# 02_MISC.net
KiCad netlist of a schematic drawn in Altium Designer
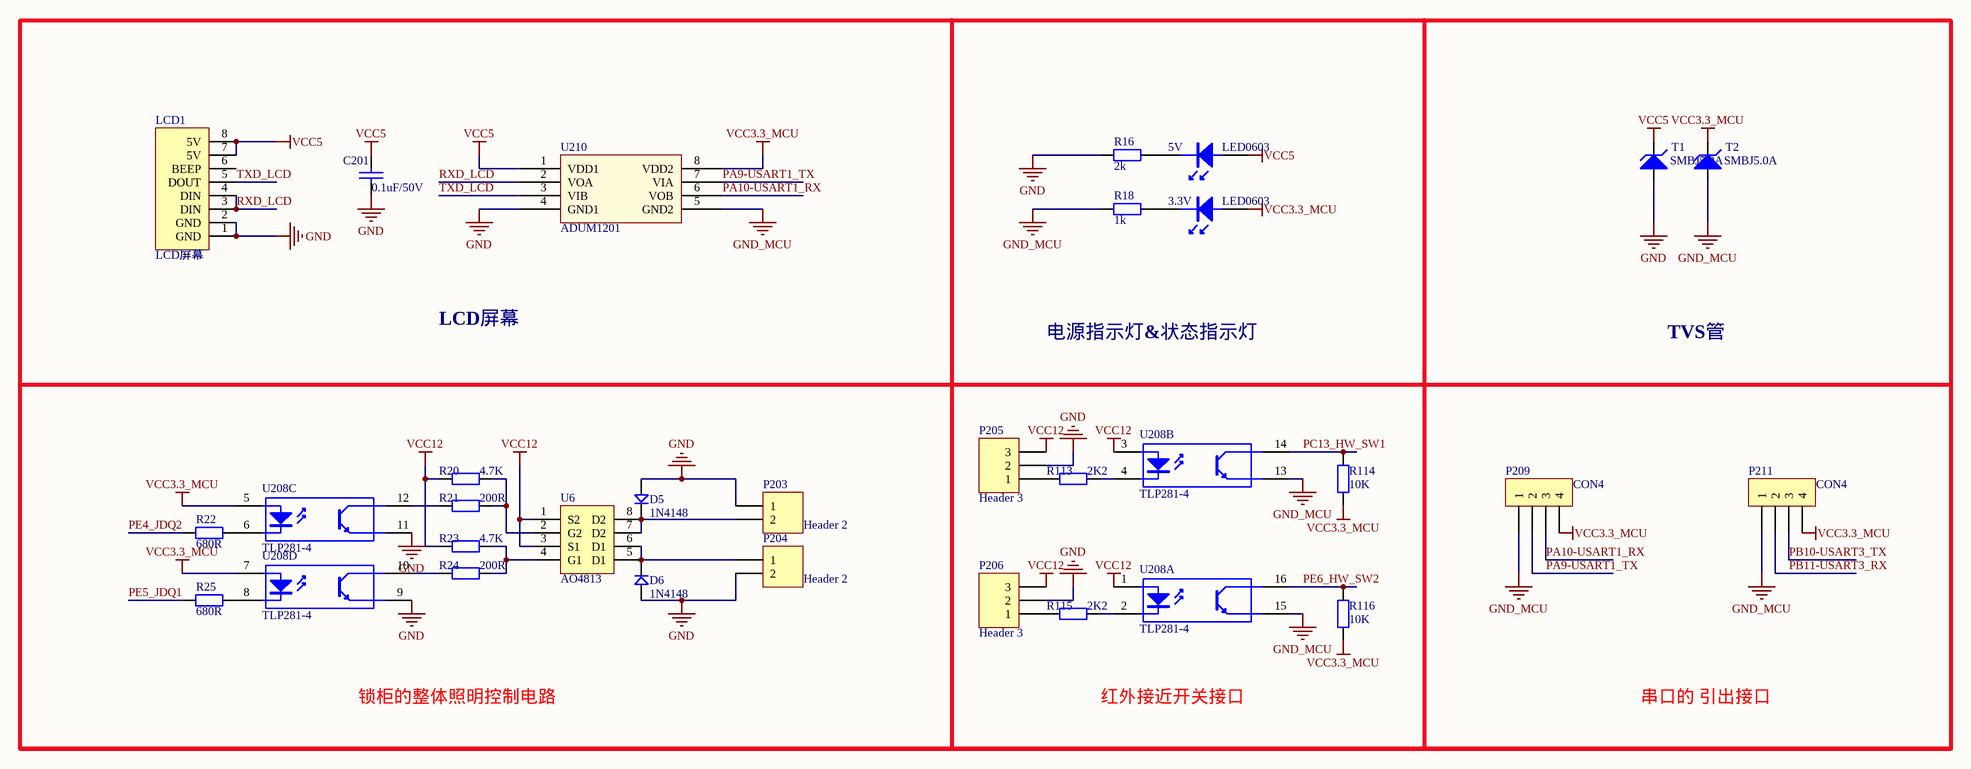
[diagram p0: 02_MISC.SchDoc]

(export (version "E")
  (design (tool "Eeschema 10.0.6"))
  (components
    (comp (ref "3.3V")
      (value "LED0603")
      (footprint "CD's_LIB_2018:0603LED")
      (description "贴片LED")
      (libsource (lib "CD's_LIB_2018") (part "LED_SMD"))
    )
    (comp (ref "5V")
      (value "LED0603")
      (footprint "CD's_LIB_2018:0603LED")
      (description "贴片LED")
      (libsource (lib "CD's_LIB_2018") (part "LED_SMD"))
    )
    (comp (ref "C201")
      (value "0.1uF/50V")
      (footprint "CD's_LIB_2018:0805C")
      (description "Capacitor")
      (libsource (lib "*") (part "CAP"))
    )
    (comp (ref "D5")
      (value "1N4148")
      (footprint "D1812")
      (libsource (lib "Explorer STM32F407封装库") (part "D"))
    )
    (comp (ref "D6")
      (value "1N4148")
      (footprint "D1812")
      (libsource (lib "Explorer STM32F407封装库") (part "D"))
    )
    (comp (ref "LCD1")
      (value "LCD屏幕")
      (footprint "lcd_JIEKOU")
      (libsource (lib "串口LCD") (part "Component_1"))
    )
    (comp (ref "P203")
      (value "Header 2")
      (footprint "HEAD2L-0.8")
      (description "Header, 2-Pin")
      (fields (field (name "PUBLISHER") "Altium Limited"))
      (libsource (lib "Sparks") (part "Header 2"))
    )
    (comp (ref "P204")
      (value "Header 2")
      (footprint "HEAD2L-0.8")
      (description "Header, 2-Pin")
      (fields (field (name "PUBLISHER") "Altium Limited"))
      (libsource (lib "Sparks") (part "Header 2"))
    )
    (comp (ref "P205")
      (value "Header 3")
      (footprint "HDR1X3")
      (description "Header, 3-Pin")
      (fields (field (name "PUBLISHER") "Altium Limited"))
      (libsource (lib "Sparks") (part "Header 3"))
    )
    (comp (ref "P206")
      (value "Header 3")
      (footprint "HDR1X3")
      (description "Header, 3-Pin")
      (fields (field (name "PUBLISHER") "Altium Limited"))
      (libsource (lib "Sparks") (part "Header 3"))
    )
    (comp (ref "P209")
      (value "CON4")
      (footprint "SIP4")
      (description "Connector")
      (libsource (lib "CD's_LIB_2018") (part "CON4"))
    )
    (comp (ref "P211")
      (value "CON4")
      (footprint "SIP4")
      (description "Connector")
      (libsource (lib "CD's_LIB_2018") (part "CON4"))
    )
    (comp (ref "R16")
      (value "2k")
      (footprint "0603R")
      (description "贴片电阻")
      (fields (field (name "PUBLISHER") "Altium Limited"))
      (libsource (lib "liu_2016") (part "Res1"))
    )
    (comp (ref "R18")
      (value "1k")
      (footprint "0603R")
      (description "贴片电阻")
      (fields (field (name "PUBLISHER") "Altium Limited"))
      (libsource (lib "liu_2016") (part "Res1"))
    )
    (comp (ref "R20")
      (value "4.7K")
      (footprint "0603R")
      (description "贴片电阻")
      (libsource (lib "") (part "0603 2.7KΩ (2701) 1%_1"))
    )
    (comp (ref "R21")
      (value "200R")
      (footprint "0603R")
      (description "贴片电阻")
      (libsource (lib "Miscellaneous Devices LC") (part "0603 2.7KΩ (2701) 1%"))
    )
    (comp (ref "R22")
      (value "680R")
      (footprint "0603R")
      (description "贴片电阻")
      (libsource (lib "Miscellaneous Devices LC") (part "0603 2.7KΩ (2701) 1%"))
    )
    (comp (ref "R23")
      (value "4.7K")
      (footprint "0603R")
      (description "贴片电阻")
      (libsource (lib "") (part "0603 2.7KΩ (2701) 1%_1"))
    )
    (comp (ref "R24")
      (value "200R")
      (footprint "0603R")
      (description "贴片电阻")
      (libsource (lib "Miscellaneous Devices LC") (part "0603 2.7KΩ (2701) 1%"))
    )
    (comp (ref "R25")
      (value "680R")
      (footprint "0603R")
      (description "贴片电阻")
      (libsource (lib "Miscellaneous Devices LC") (part "0603 2.7KΩ (2701) 1%"))
    )
    (comp (ref "R113")
      (value "2K2")
      (footprint "0603R")
      (description "贴片电阻")
      (libsource (lib "Miscellaneous Devices LC") (part "0603 2.7KΩ (2701) 1%"))
    )
    (comp (ref "R114")
      (value "10K")
      (footprint "0603R")
      (description "贴片电阻")
      (libsource (lib "") (part "0603 2.7KΩ (2701) 1%_2"))
    )
    (comp (ref "R115")
      (value "2K2")
      (footprint "0603R")
      (description "贴片电阻")
      (libsource (lib "Miscellaneous Devices LC") (part "0603 2.7KΩ (2701) 1%"))
    )
    (comp (ref "R116")
      (value "10K")
      (footprint "0603R")
      (description "贴片电阻")
      (libsource (lib "") (part "0603 2.7KΩ (2701) 1%_2"))
    )
    (comp (ref "T1")
      (value "SMBJ5.0A")
      (footprint "D1812")
      (description "Zener Diode")
      (libsource (lib "*") (part "SS36"))
    )
    (comp (ref "T2")
      (value "SMBJ5.0A")
      (footprint "D1812")
      (description "Zener Diode")
      (libsource (lib "*") (part "SS36"))
    )
    (comp (ref "U6") (value "AO4813") (footprint "SO-8") (libsource (lib "NDS8434") (part "NDS8434")))
    (comp (ref "U208")
      (value "TLP281-4")
      (footprint "SO-16")
      (libsource (lib "CD's_LIB_2018") (part "TP521-4_1"))
    )
    (comp (ref "U210")
      (value "ADUM1201")
      (footprint "SOP_8")
      (description "串口隔离")
      (libsource (lib "liu_2016") (part "ADUM1201"))
    )
  )
  (nets
    (net (code "1") (name "/PA9-USART1_TX") (class "Default")
      (node (ref "P209") (pin "2") (pinfunction "2_2") (pintype "passive"))
      (node (ref "U210") (pin "7") (pinfunction "VIA_7") (pintype "passive"))
    )
    (net (code "2") (name "/PA10-USART1_RX") (class "Default")
      (node (ref "P209") (pin "3") (pinfunction "3_3") (pintype "passive"))
      (node (ref "U210") (pin "6") (pinfunction "VOB_6") (pintype "passive"))
    )
    (net (code "3") (name "/PB10-USART3_TX") (class "Default")
      (node (ref "P211") (pin "3") (pinfunction "3_3") (pintype "passive"))
    )
    (net (code "4") (name "/PB11-USART3_RX") (class "Default")
      (node (ref "P211") (pin "2") (pinfunction "2_2") (pintype "passive"))
    )
    (net (code "5") (name "/PC13_HW_SW1") (class "Default")
      (node (ref "R114") (pin "2") (pinfunction "2_2") (pintype "passive"))
      (node (ref "U208") (pin "14") (pinfunction "C_14") (pintype "passive"))
    )
    (net (code "6") (name "/PE4_JDQ2") (class "Default")
      (node (ref "R22") (pin "1") (pinfunction "1_1") (pintype "passive"))
    )
    (net (code "7") (name "/PE5_JDQ1") (class "Default")
      (node (ref "R25") (pin "1") (pinfunction "1_1") (pintype "passive"))
    )
    (net (code "8") (name "/PE6_HW_SW2") (class "Default")
      (node (ref "R116") (pin "2") (pinfunction "2_2") (pintype "passive"))
      (node (ref "U208") (pin "16") (pinfunction "C_16") (pintype "passive"))
    )
    (net (code "9") (name "/RXD_LCD") (class "Default")
      (node (ref "LCD1") (pin "3") (pinfunction "DIN_3") (pintype "passive"))
      (node (ref "LCD1") (pin "4") (pinfunction "DIN_4") (pintype "passive"))
      (node (ref "U210") (pin "2") (pinfunction "VOA_2") (pintype "passive"))
    )
    (net (code "10") (name "/TXD_LCD") (class "Default")
      (node (ref "LCD1") (pin "5") (pinfunction "DOUT_5") (pintype "passive"))
      (node (ref "U210") (pin "3") (pinfunction "VIB_3") (pintype "passive"))
    )
    (net (code "11") (name "GND") (class "Default")
      (node (ref "C201") (pin "2") (pinfunction "2_2") (pintype "passive"))
      (node (ref "D5") (pin "1") (pintype "passive"))
      (node (ref "D6") (pin "1") (pintype "passive"))
      (node (ref "LCD1") (pin "1") (pinfunction "GND_1") (pintype "passive"))
      (node (ref "LCD1") (pin "2") (pinfunction "GND_2") (pintype "passive"))
      (node (ref "P203") (pin "1") (pinfunction "1_1") (pintype "passive"))
      (node (ref "P204") (pin "2") (pinfunction "2_2") (pintype "passive"))
      (node (ref "P205") (pin "2") (pinfunction "2_2") (pintype "passive"))
      (node (ref "P206") (pin "2") (pinfunction "2_2") (pintype "passive"))
      (node (ref "R16") (pin "1") (pinfunction "1_1") (pintype "passive"))
      (node (ref "T1") (pin "1") (pinfunction "A_1") (pintype "passive"))
      (node (ref "U208") (pin "11") (pinfunction "E_11") (pintype "passive"))
      (node (ref "U208") (pin "9") (pinfunction "E_9") (pintype "passive"))
      (node (ref "U210") (pin "4") (pinfunction "GND1_4") (pintype "passive"))
    )
    (net (code "12") (name "GND_MCU") (class "Default")
      (node (ref "P209") (pin "1") (pinfunction "1_1") (pintype "passive"))
      (node (ref "P211") (pin "1") (pinfunction "1_1") (pintype "passive"))
      (node (ref "R18") (pin "1") (pinfunction "1_1") (pintype "passive"))
      (node (ref "T2") (pin "1") (pinfunction "A_1") (pintype "passive"))
      (node (ref "U208") (pin "13") (pinfunction "E_13") (pintype "passive"))
      (node (ref "U208") (pin "15") (pinfunction "E_15") (pintype "passive"))
      (node (ref "U210") (pin "5") (pinfunction "GND2_5") (pintype "passive"))
    )
    (net (code "13") (name "Net-(3.3V--)") (class "Default")
      (node (ref "3.3V") (pin "1") (pinfunction "-_1") (pintype "passive"))
      (node (ref "R18") (pin "2") (pinfunction "2_2") (pintype "passive"))
    )
    (net (code "14") (name "Net-(5V--)") (class "Default")
      (node (ref "5V") (pin "1") (pinfunction "-_1") (pintype "passive"))
      (node (ref "R16") (pin "2") (pinfunction "2_2") (pintype "passive"))
    )
    (net (code "15") (name "Net-(D5-Pad2)") (class "Default")
      (node (ref "D5") (pin "2") (pintype "passive"))
      (node (ref "P203") (pin "2") (pinfunction "2_2") (pintype "passive"))
      (node (ref "U6") (pin "7") (pinfunction "D2_7") (pintype "passive"))
      (node (ref "U6") (pin "8") (pinfunction "D2_8") (pintype "passive"))
    )
    (net (code "16") (name "Net-(D6-Pad2)") (class "Default")
      (node (ref "D6") (pin "2") (pintype "passive"))
      (node (ref "P204") (pin "1") (pinfunction "1_1") (pintype "passive"))
      (node (ref "U6") (pin "5") (pinfunction "D1_5") (pintype "passive"))
      (node (ref "U6") (pin "6") (pinfunction "D1_6") (pintype "passive"))
    )
    (net (code "17") (name "Net-(P205-Pad1)") (class "Default")
      (node (ref "P205") (pin "1") (pinfunction "1_1") (pintype "passive"))
      (node (ref "R113") (pin "1") (pinfunction "1_1") (pintype "passive"))
    )
    (net (code "18") (name "Net-(P206-Pad1)") (class "Default")
      (node (ref "P206") (pin "1") (pinfunction "1_1") (pintype "passive"))
      (node (ref "R115") (pin "1") (pinfunction "1_1") (pintype "passive"))
    )
    (net (code "19") (name "Net-(U6-G1)") (class "Default")
      (node (ref "R23") (pin "1") (pinfunction "1_1") (pintype "passive"))
      (node (ref "R24") (pin "2") (pinfunction "2_2") (pintype "passive"))
      (node (ref "U6") (pin "4") (pinfunction "G1_4") (pintype "passive"))
    )
    (net (code "20") (name "Net-(U6-G2)") (class "Default")
      (node (ref "R20") (pin "1") (pinfunction "1_1") (pintype "passive"))
      (node (ref "R21") (pin "2") (pinfunction "2_2") (pintype "passive"))
      (node (ref "U6") (pin "2") (pinfunction "G2_2") (pintype "passive"))
    )
    (net (code "21") (name "Net-(U208A-K)") (class "Default")
      (node (ref "R115") (pin "2") (pinfunction "2_2") (pintype "passive"))
      (node (ref "U208") (pin "2") (pinfunction "K_2") (pintype "passive"))
    )
    (net (code "22") (name "Net-(U208B-K)") (class "Default")
      (node (ref "R113") (pin "2") (pinfunction "2_2") (pintype "passive"))
      (node (ref "U208") (pin "4") (pinfunction "K_4") (pintype "passive"))
    )
    (net (code "23") (name "Net-(U208C-C)") (class "Default")
      (node (ref "R21") (pin "1") (pinfunction "1_1") (pintype "passive"))
      (node (ref "U208") (pin "12") (pinfunction "C_12") (pintype "passive"))
    )
    (net (code "24") (name "Net-(U208C-K)") (class "Default")
      (node (ref "R22") (pin "2") (pinfunction "2_2") (pintype "passive"))
      (node (ref "U208") (pin "6") (pinfunction "K_6") (pintype "passive"))
    )
    (net (code "25") (name "Net-(U208D-C)") (class "Default")
      (node (ref "R24") (pin "1") (pinfunction "1_1") (pintype "passive"))
      (node (ref "U208") (pin "10") (pinfunction "C_10") (pintype "passive"))
    )
    (net (code "26") (name "Net-(U208D-K)") (class "Default")
      (node (ref "R25") (pin "2") (pinfunction "2_2") (pintype "passive"))
      (node (ref "U208") (pin "8") (pinfunction "K_8") (pintype "passive"))
    )
    (net (code "27") (name "VCC3.3_MCU") (class "Default")
      (node (ref "3.3V") (pin "2") (pinfunction "+_2") (pintype "passive"))
      (node (ref "P209") (pin "4") (pinfunction "4_4") (pintype "passive"))
      (node (ref "P211") (pin "4") (pinfunction "4_4") (pintype "passive"))
      (node (ref "R114") (pin "1") (pinfunction "1_1") (pintype "passive"))
      (node (ref "R116") (pin "1") (pinfunction "1_1") (pintype "passive"))
      (node (ref "T2") (pin "2") (pinfunction "K_2") (pintype "passive"))
      (node (ref "U208") (pin "5") (pinfunction "A_5") (pintype "passive"))
      (node (ref "U208") (pin "7") (pinfunction "A_7") (pintype "passive"))
      (node (ref "U210") (pin "8") (pinfunction "VDD2_8") (pintype "passive"))
    )
    (net (code "28") (name "VCC5") (class "Default")
      (node (ref "5V") (pin "2") (pinfunction "+_2") (pintype "passive"))
      (node (ref "C201") (pin "1") (pinfunction "1_1") (pintype "passive"))
      (node (ref "LCD1") (pin "7") (pinfunction "5V_7") (pintype "passive"))
      (node (ref "LCD1") (pin "8") (pinfunction "5V_8") (pintype "passive"))
      (node (ref "T1") (pin "2") (pinfunction "K_2") (pintype "passive"))
      (node (ref "U210") (pin "1") (pinfunction "VDD1_1") (pintype "passive"))
    )
    (net (code "29") (name "VCC12") (class "Default")
      (node (ref "P205") (pin "3") (pinfunction "3_3") (pintype "passive"))
      (node (ref "P206") (pin "3") (pinfunction "3_3") (pintype "passive"))
      (node (ref "R20") (pin "2") (pinfunction "2_2") (pintype "passive"))
      (node (ref "R23") (pin "2") (pinfunction "2_2") (pintype "passive"))
      (node (ref "U208") (pin "1") (pinfunction "A_1") (pintype "passive"))
      (node (ref "U208") (pin "3") (pinfunction "A_3") (pintype "passive"))
      (node (ref "U6") (pin "1") (pinfunction "S2_1") (pintype "passive"))
      (node (ref "U6") (pin "3") (pinfunction "S1_3") (pintype "passive"))
    )
    (net (code "30") (name "unconnected-(LCD1-BEEP-Pad6)") (class "Default")
      (node (ref "LCD1") (pin "6") (pinfunction "BEEP_6") (pintype "passive"))
    )
  )
)
